# PB-Interface.net
KiCad netlist of a schematic drawn in EAGLE
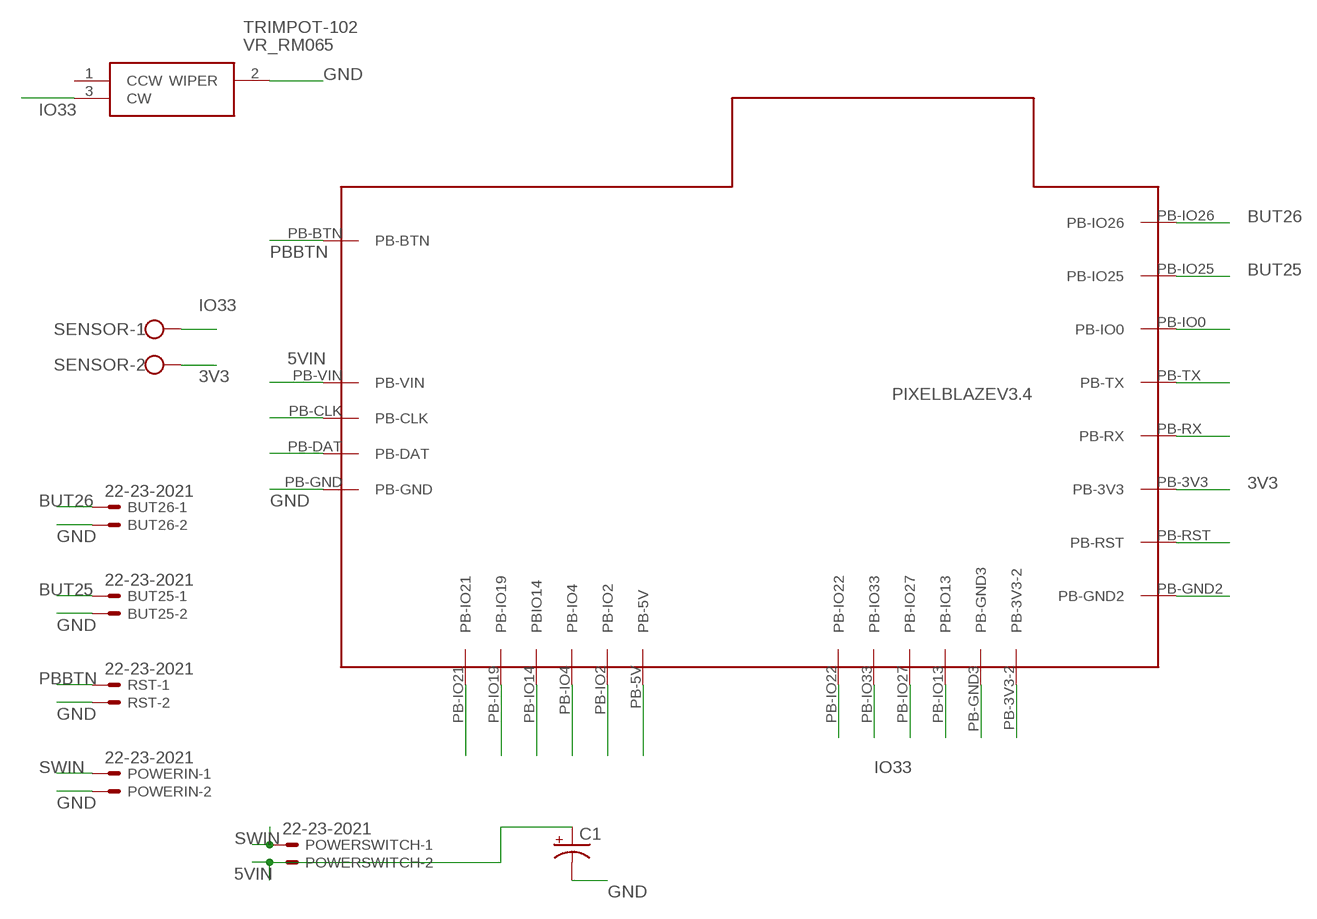
[diagram p0: schematic, sheet 1]

(export (version "E")
  (design (tool "Eeschema 10.0.6"))
  (components
    (comp (ref "BUT25")
      (value "22-23-2021")
      (footprint "eagle-import:22-23-2021")
      (fields (field (name "MF") "MOLEX"))
      (libsource (lib "eagle-import") (part "22-23-2021"))
    )
    (comp (ref "BUT26")
      (value "22-23-2021")
      (footprint "eagle-import:22-23-2021")
      (fields (field (name "MF") "MOLEX"))
      (libsource (lib "eagle-import") (part "22-23-2021"))
    )
    (comp (ref "C1")
      (value "CPOL-USE5-10.5")
      (footprint "eagle-import:E5-10,5")
      (libsource (lib "eagle-import") (part "CPOL-USE5-10.5"))
    )
    (comp (ref "PIXELBLAZEV3.4")
      (value "PIXELBLAZE-V3.4")
      (footprint "eagle-import:PIXELBLAZE-V3")
      (libsource (lib "eagle-import") (part "PIXELBLAZE-V3.4"))
    )
    (comp (ref "POWERIN")
      (value "22-23-2021")
      (footprint "eagle-import:22-23-2021")
      (fields (field (name "MF") "MOLEX"))
      (libsource (lib "eagle-import") (part "22-23-2021"))
    )
    (comp (ref "POWERSWITCH")
      (value "22-23-2021")
      (footprint "eagle-import:22-23-2021")
      (fields (field (name "MF") "MOLEX"))
      (libsource (lib "eagle-import") (part "22-23-2021"))
    )
    (comp (ref "RST")
      (value "22-23-2021")
      (footprint "eagle-import:22-23-2021")
      (fields (field (name "MF") "MOLEX"))
      (libsource (lib "eagle-import") (part "22-23-2021"))
    )
    (comp (ref "SENSOR")
      (value "W237-102")
      (footprint "eagle-import:W237-102")
      (fields (field (name "MPN") "237-102"))
      (libsource (lib "eagle-import") (part "W237-102"))
    )
    (comp (ref "TRIMPOT-102")
      (value "VR_RM065")
      (footprint "eagle-import:VRRM065")
      (fields (field (name "MANUFACTURER_PART_NUMBER") "VR RM065"))
      (libsource (lib "eagle-import") (part "VR_RM065"))
    )
  )
  (nets
    (net (code "1") (name "/3V3") (class "Default")
      (node (ref "PIXELBLAZEV3.4") (pin "PB-3V3") (pinfunction "PB-3V3_PB-3V3") (pintype "bidirectional"))
      (node (ref "SENSOR") (pin "2") (pinfunction "KL_2") (pintype "passive"))
    )
    (net (code "2") (name "/5VIN") (class "Default")
      (node (ref "C1") (pin "+") (pinfunction "+_+") (pintype "passive"))
      (node (ref "PIXELBLAZEV3.4") (pin "PB-VIN") (pinfunction "PB-VIN_PB-VIN") (pintype "bidirectional"))
      (node (ref "POWERSWITCH") (pin "2") (pinfunction "S_2") (pintype "passive"))
    )
    (net (code "3") (name "/BUT25") (class "Default")
      (node (ref "BUT25") (pin "1") (pinfunction "S_1") (pintype "passive"))
      (node (ref "PIXELBLAZEV3.4") (pin "PB-IO25") (pinfunction "PB-IO25_PB-IO25") (pintype "bidirectional"))
    )
    (net (code "4") (name "/BUT26") (class "Default")
      (node (ref "BUT26") (pin "1") (pinfunction "S_1") (pintype "passive"))
      (node (ref "PIXELBLAZEV3.4") (pin "PB-IO26") (pinfunction "PB-IO26_PB-IO26") (pintype "bidirectional"))
    )
    (net (code "5") (name "/GND") (class "Default")
      (node (ref "BUT25") (pin "2") (pinfunction "S_2") (pintype "passive"))
      (node (ref "BUT26") (pin "2") (pinfunction "S_2") (pintype "passive"))
      (node (ref "C1") (pin "-") (pinfunction "-_-") (pintype "passive"))
      (node (ref "PIXELBLAZEV3.4") (pin "PB-GND") (pinfunction "PB-GND_PB-GND") (pintype "bidirectional"))
      (node (ref "POWERIN") (pin "2") (pinfunction "S_2") (pintype "passive"))
      (node (ref "RST") (pin "2") (pinfunction "S_2") (pintype "passive"))
      (node (ref "TRIMPOT-102") (pin "2") (pinfunction "WIPER_2") (pintype "bidirectional"))
    )
    (net (code "6") (name "/IO33") (class "Default")
      (node (ref "PIXELBLAZEV3.4") (pin "PB-IO33") (pinfunction "PB-IO33_PB-IO33") (pintype "bidirectional"))
      (node (ref "SENSOR") (pin "1") (pinfunction "KL_1") (pintype "passive"))
      (node (ref "TRIMPOT-102") (pin "3") (pinfunction "CW_3") (pintype "bidirectional"))
    )
    (net (code "7") (name "/PBBTN") (class "Default")
      (node (ref "PIXELBLAZEV3.4") (pin "PB-BTN") (pinfunction "PB-BTN_PB-BTN") (pintype "bidirectional"))
      (node (ref "RST") (pin "1") (pinfunction "S_1") (pintype "passive"))
    )
    (net (code "8") (name "/SWIN") (class "Default")
      (node (ref "POWERIN") (pin "1") (pinfunction "S_1") (pintype "passive"))
      (node (ref "POWERSWITCH") (pin "1") (pinfunction "S_1") (pintype "passive"))
    )
    (net (code "9") (name "unconnected-(PIXELBLAZEV3.4-PBIO14-PadPB-IO14)") (class "Default")
      (node (ref "PIXELBLAZEV3.4") (pin "PB-IO14") (pinfunction "PBIO14_PB-IO14") (pintype "bidirectional"))
    )
    (net (code "10") (name "unconnected-(PIXELBLAZEV3.4-PadPB-3V3-2)") (class "Default")
      (node (ref "PIXELBLAZEV3.4") (pin "PB-3V3-2") (pinfunction "PB-3V3-2_PB-3V3-2") (pintype "bidirectional"))
    )
    (net (code "11") (name "unconnected-(PIXELBLAZEV3.4-PadPB-5V)") (class "Default")
      (node (ref "PIXELBLAZEV3.4") (pin "PB-5V") (pinfunction "PB-5V_PB-5V") (pintype "bidirectional"))
    )
    (net (code "12") (name "unconnected-(PIXELBLAZEV3.4-PadPB-CLK)") (class "Default")
      (node (ref "PIXELBLAZEV3.4") (pin "PB-CLK") (pinfunction "PB-CLK_PB-CLK") (pintype "bidirectional"))
    )
    (net (code "13") (name "unconnected-(PIXELBLAZEV3.4-PadPB-DAT)") (class "Default")
      (node (ref "PIXELBLAZEV3.4") (pin "PB-DAT") (pinfunction "PB-DAT_PB-DAT") (pintype "bidirectional"))
    )
    (net (code "14") (name "unconnected-(PIXELBLAZEV3.4-PadPB-GND2)") (class "Default")
      (node (ref "PIXELBLAZEV3.4") (pin "PB-GND2") (pinfunction "PB-GND2_PB-GND2") (pintype "bidirectional"))
    )
    (net (code "15") (name "unconnected-(PIXELBLAZEV3.4-PadPB-GND3)") (class "Default")
      (node (ref "PIXELBLAZEV3.4") (pin "PB-GND3") (pinfunction "PB-GND3_PB-GND3") (pintype "bidirectional"))
    )
    (net (code "16") (name "unconnected-(PIXELBLAZEV3.4-PadPB-IO0)") (class "Default")
      (node (ref "PIXELBLAZEV3.4") (pin "PB-IO0") (pinfunction "PB-IO0_PB-IO0") (pintype "bidirectional"))
    )
    (net (code "17") (name "unconnected-(PIXELBLAZEV3.4-PadPB-IO2)") (class "Default")
      (node (ref "PIXELBLAZEV3.4") (pin "PB-IO2") (pinfunction "PB-IO2_PB-IO2") (pintype "bidirectional"))
    )
    (net (code "18") (name "unconnected-(PIXELBLAZEV3.4-PadPB-IO4)") (class "Default")
      (node (ref "PIXELBLAZEV3.4") (pin "PB-IO4") (pinfunction "PB-IO4_PB-IO4") (pintype "bidirectional"))
    )
    (net (code "19") (name "unconnected-(PIXELBLAZEV3.4-PadPB-IO13)") (class "Default")
      (node (ref "PIXELBLAZEV3.4") (pin "PB-IO13") (pinfunction "PB-IO13_PB-IO13") (pintype "bidirectional"))
    )
    (net (code "20") (name "unconnected-(PIXELBLAZEV3.4-PadPB-IO19)") (class "Default")
      (node (ref "PIXELBLAZEV3.4") (pin "PB-IO19") (pinfunction "PB-IO19_PB-IO19") (pintype "bidirectional"))
    )
    (net (code "21") (name "unconnected-(PIXELBLAZEV3.4-PadPB-IO21)") (class "Default")
      (node (ref "PIXELBLAZEV3.4") (pin "PB-IO21") (pinfunction "PB-IO21_PB-IO21") (pintype "bidirectional"))
    )
    (net (code "22") (name "unconnected-(PIXELBLAZEV3.4-PadPB-IO22)") (class "Default")
      (node (ref "PIXELBLAZEV3.4") (pin "PB-IO22") (pinfunction "PB-IO22_PB-IO22") (pintype "bidirectional"))
    )
    (net (code "23") (name "unconnected-(PIXELBLAZEV3.4-PadPB-IO27)") (class "Default")
      (node (ref "PIXELBLAZEV3.4") (pin "PB-IO27") (pinfunction "PB-IO27_PB-IO27") (pintype "bidirectional"))
    )
    (net (code "24") (name "unconnected-(PIXELBLAZEV3.4-PadPB-RST)") (class "Default")
      (node (ref "PIXELBLAZEV3.4") (pin "PB-RST") (pinfunction "PB-RST_PB-RST") (pintype "bidirectional"))
    )
    (net (code "25") (name "unconnected-(PIXELBLAZEV3.4-PadPB-RX)") (class "Default")
      (node (ref "PIXELBLAZEV3.4") (pin "PB-RX") (pinfunction "PB-RX_PB-RX") (pintype "bidirectional"))
    )
    (net (code "26") (name "unconnected-(PIXELBLAZEV3.4-PadPB-TX)") (class "Default")
      (node (ref "PIXELBLAZEV3.4") (pin "PB-TX") (pinfunction "PB-TX_PB-TX") (pintype "bidirectional"))
    )
    (net (code "27") (name "unconnected-(TRIMPOT-102-CCW-Pad1)") (class "Default")
      (node (ref "TRIMPOT-102") (pin "1") (pinfunction "CCW_1") (pintype "bidirectional"))
    )
  )
)
